# ATTINY85_feeder.net
KiCad netlist of a schematic drawn in EAGLE
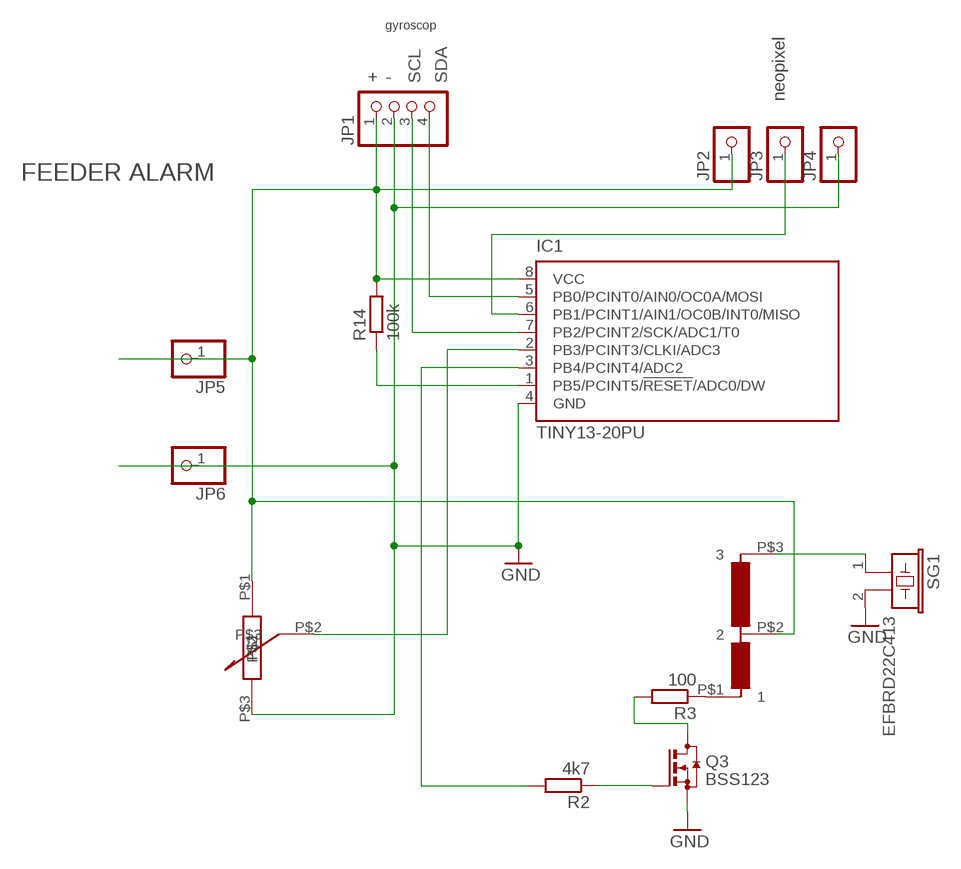
[diagram p0: schematic, sheet 1]

(export (version "E")
  (design (tool "Eeschema 10.0.6"))
  (components
    (comp (ref "IC1")
      (value "TINY13-20PU")
      (footprint "eagle-import:DIL08")
      (fields (field (name "MPN") "ATTINY13-20PU"))
      (libsource (lib "eagle-import") (part "TINY13PU-20"))
    )
    (comp (ref "JP1")
      (value "PINHD-1X4")
      (footprint "eagle-import:1X04")
      (libsource (lib "eagle-import") (part "PINHD-1X4"))
    )
    (comp (ref "JP2")
      (value "PINHD-1X1")
      (footprint "eagle-import:1X01")
      (libsource (lib "eagle-import") (part "PINHD-1X1"))
    )
    (comp (ref "JP3")
      (value "PINHD-1X1")
      (footprint "eagle-import:1X01")
      (libsource (lib "eagle-import") (part "PINHD-1X1"))
    )
    (comp (ref "JP4")
      (value "PINHD-1X1")
      (footprint "eagle-import:1X01")
      (libsource (lib "eagle-import") (part "PINHD-1X1"))
    )
    (comp (ref "JP5")
      (value "PINHD-1X1")
      (footprint "eagle-import:1X01")
      (libsource (lib "eagle-import") (part "PINHD-1X1"))
    )
    (comp (ref "JP6")
      (value "PINHD-1X1")
      (footprint "eagle-import:1X01")
      (libsource (lib "eagle-import") (part "PINHD-1X1"))
    )
    (comp (ref "Q3")
      (value "BSS123")
      (footprint "eagle-import:SOT23")
      (libsource (lib "eagle-import") (part "BSS123"))
    )
    (comp (ref "R2")
      (value "4k7")
      (footprint "eagle-import:0204_7")
      (libsource (lib "eagle-import") (part "R-EU_0204/7"))
    )
    (comp (ref "R3")
      (value "100")
      (footprint "eagle-import:0204_7")
      (libsource (lib "eagle-import") (part "R-EU_0204/7"))
    )
    (comp (ref "R14")
      (value "100k")
      (footprint "eagle-import:0204_7")
      (libsource (lib "eagle-import") (part "R-EU_0204/7"))
    )
    (comp (ref "SG1")
      (value "EFBRD22C413")
      (footprint "eagle-import:EFBRD22C413")
      (libsource (lib "eagle-import") (part "EFB?RD22C413"))
    )
    (comp (ref "U$1")
      (value "POTENCIOMETER")
      (footprint "eagle-import:POTENCIOMETER")
      (libsource (lib "eagle-import") (part "POTENCIOMETER"))
    )
    (comp (ref "U$3")
      (value "AUTOTRAFO")
      (footprint "eagle-import:AUTOTRAFO")
      (libsource (lib "eagle-import") (part "AUTOTRAFO"))
    )
  )
  (nets
    (net (code "1") (name "GND") (class "Default")
      (node (ref "IC1") (pin "4") (pinfunction "GND_4") (pintype "power_in"))
      (node (ref "JP1") (pin "2") (pinfunction "2_2") (pintype "passive"))
      (node (ref "JP4") (pin "1") (pinfunction "1_1") (pintype "passive"))
      (node (ref "JP6") (pin "1") (pinfunction "1_1") (pintype "passive"))
      (node (ref "Q3") (pin "2") (pinfunction "S_2") (pintype "passive"))
      (node (ref "SG1") (pin "2") (pinfunction "2_2") (pintype "passive"))
      (node (ref "U$1") (pin "P$3") (pinfunction "P$2_P$3") (pintype "bidirectional"))
    )
    (net (code "2") (name "Net-(IC1-PB0{slash}PCINT0{slash}AIN0{slash}OC0A{slash}MOSI)") (class "Default")
      (node (ref "IC1") (pin "5") (pinfunction "PB0/PCINT0/AIN0/OC0A/MOSI_5") (pintype "bidirectional"))
      (node (ref "JP1") (pin "4") (pinfunction "4_4") (pintype "passive"))
    )
    (net (code "3") (name "Net-(IC1-PB1{slash}PCINT1{slash}AIN1{slash}OC0B{slash}INT0{slash}MISO)") (class "Default")
      (node (ref "IC1") (pin "6") (pinfunction "PB1/PCINT1/AIN1/OC0B/INT0/MISO_6") (pintype "bidirectional"))
      (node (ref "JP3") (pin "1") (pinfunction "1_1") (pintype "passive"))
    )
    (net (code "4") (name "Net-(IC1-PB2{slash}PCINT2{slash}SCK{slash}ADC1{slash}T0)") (class "Default")
      (node (ref "IC1") (pin "7") (pinfunction "PB2/PCINT2/SCK/ADC1/T0_7") (pintype "bidirectional"))
      (node (ref "JP1") (pin "3") (pinfunction "3_3") (pintype "passive"))
    )
    (net (code "5") (name "Net-(IC1-PB3{slash}PCINT3{slash}CLKI{slash}ADC3)") (class "Default")
      (node (ref "IC1") (pin "2") (pinfunction "PB3/PCINT3/CLKI/ADC3_2") (pintype "bidirectional"))
      (node (ref "U$1") (pin "P$2") (pinfunction "P$3_P$2") (pintype "bidirectional"))
    )
    (net (code "6") (name "Net-(IC1-PB4{slash}PCINT4{slash}ADC2)") (class "Default")
      (node (ref "IC1") (pin "3") (pinfunction "PB4/PCINT4/ADC2_3") (pintype "bidirectional"))
      (node (ref "R2") (pin "2") (pinfunction "2_2") (pintype "passive"))
    )
    (net (code "7") (name "Net-(IC1-PB5{slash}PCINT5{slash}~{RESET}{slash}ADC0{slash}DW)") (class "Default")
      (node (ref "IC1") (pin "1") (pinfunction "PB5/PCINT5/~{RESET}/ADC0/DW_1") (pintype "bidirectional"))
      (node (ref "R14") (pin "1") (pinfunction "1_1") (pintype "passive"))
    )
    (net (code "8") (name "Net-(IC1-VCC)") (class "Default")
      (node (ref "IC1") (pin "8") (pinfunction "VCC_8") (pintype "power_in"))
      (node (ref "JP1") (pin "1") (pinfunction "1_1") (pintype "passive"))
      (node (ref "JP2") (pin "1") (pinfunction "1_1") (pintype "passive"))
      (node (ref "JP5") (pin "1") (pinfunction "1_1") (pintype "passive"))
      (node (ref "R14") (pin "2") (pinfunction "2_2") (pintype "passive"))
      (node (ref "U$1") (pin "P$1") (pinfunction "P$1_P$1") (pintype "bidirectional"))
      (node (ref "U$3") (pin "P$2") (pinfunction "2_P$2") (pintype "bidirectional"))
    )
    (net (code "9") (name "Net-(Q3-D)") (class "Default")
      (node (ref "Q3") (pin "3") (pinfunction "D_3") (pintype "passive"))
      (node (ref "R3") (pin "2") (pinfunction "2_2") (pintype "passive"))
    )
    (net (code "10") (name "Net-(Q3-G)") (class "Default")
      (node (ref "Q3") (pin "1") (pinfunction "G_1") (pintype "passive"))
      (node (ref "R2") (pin "1") (pinfunction "1_1") (pintype "passive"))
    )
    (net (code "11") (name "Net-(U$3-1)") (class "Default")
      (node (ref "R3") (pin "1") (pinfunction "1_1") (pintype "passive"))
      (node (ref "U$3") (pin "P$1") (pinfunction "1_P$1") (pintype "bidirectional"))
    )
    (net (code "12") (name "Net-(U$3-3)") (class "Default")
      (node (ref "SG1") (pin "1") (pinfunction "1_1") (pintype "passive"))
      (node (ref "U$3") (pin "P$3") (pinfunction "3_P$3") (pintype "bidirectional"))
    )
  )
)
